# USB.net
KiCad netlist of a schematic drawn in Altium Designer
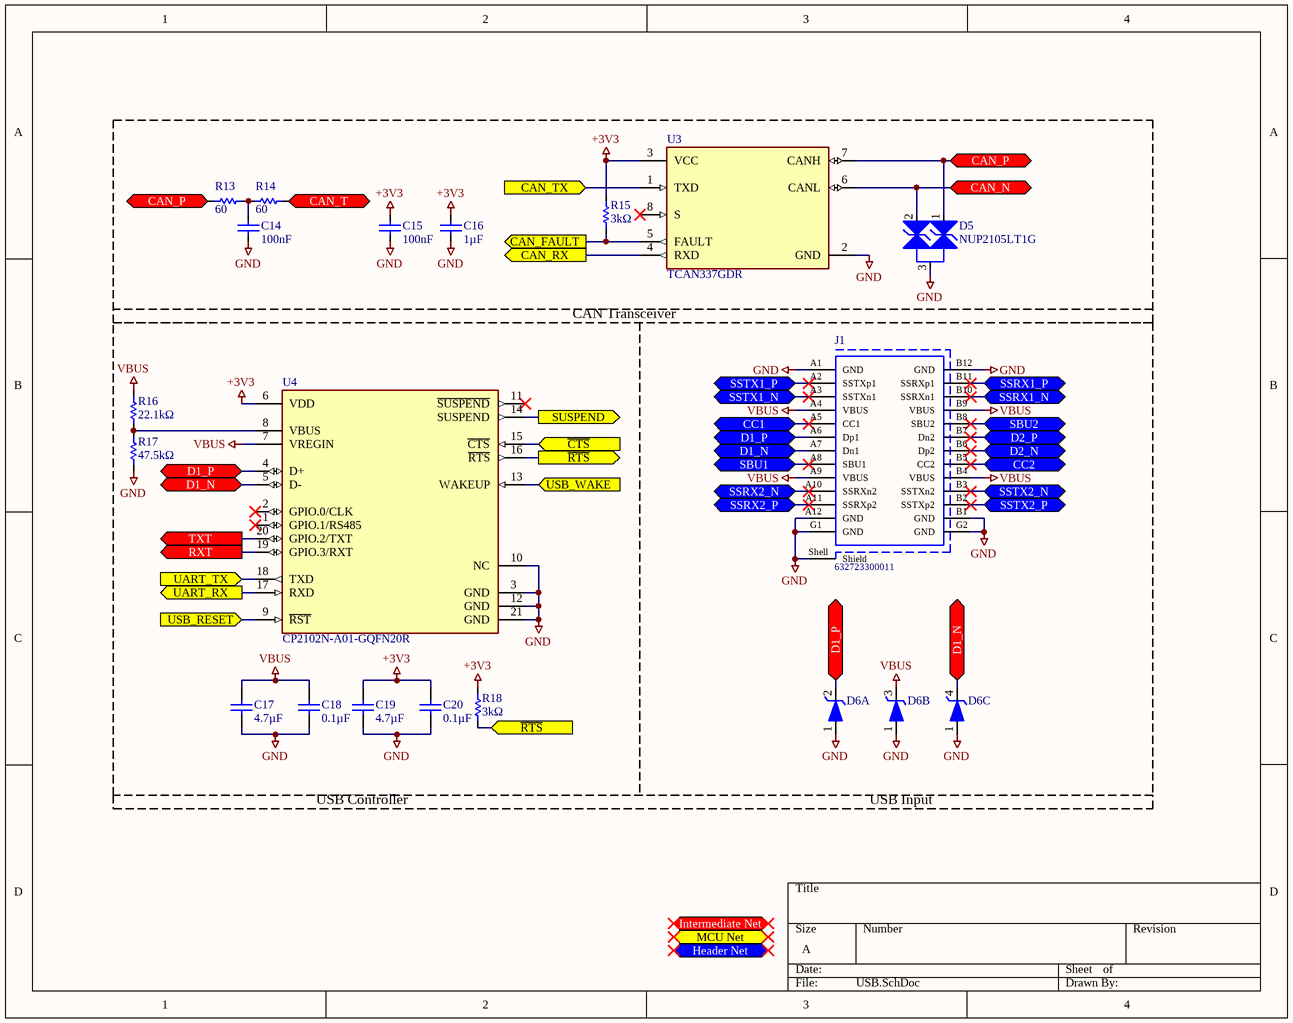
[diagram p0: USB.SchDoc]

(export (version "E")
  (design (tool "Eeschema 10.0.6"))
  (components
    (comp (ref "C14")
      (value "100nF")
      (footprint "1608[0603]")
      (description "Capacitor (Semiconductor SIM Model)")
      (fields (field (name "PUBLISHER") "Altium Limited"))
      (libsource (lib "Miscellaneous Devices") (part "Cap Semi"))
    )
    (comp (ref "C15")
      (value "100nF")
      (footprint "1608[0603]")
      (description "Capacitor (Semiconductor SIM Model)")
      (fields (field (name "PUBLISHER") "Altium Limited"))
      (libsource (lib "Miscellaneous Devices") (part "Cap Semi"))
    )
    (comp (ref "C16")
      (value "1µF")
      (footprint "1608[0603]")
      (description "Capacitor (Semiconductor SIM Model)")
      (fields (field (name "Comment") "100nF") (field (name "PUBLISHER") "Altium Limited"))
      (libsource (lib "Miscellaneous Devices") (part "Cap Semi"))
    )
    (comp (ref "C17")
      (value "4.7µF")
      (footprint "1608[0603]")
      (description "Capacitor (Semiconductor SIM Model)")
      (fields (field (name "Comment") "100nF") (field (name "PUBLISHER") "Altium Limited"))
      (libsource (lib "") (part "Cap Semi_1"))
    )
    (comp (ref "C18")
      (value "0.1µF")
      (footprint "1608[0603]")
      (description "Capacitor (Semiconductor SIM Model)")
      (fields (field (name "Comment") "100nF") (field (name "PUBLISHER") "Altium Limited"))
      (libsource (lib "") (part "Cap Semi_1"))
    )
    (comp (ref "C19")
      (value "4.7µF")
      (footprint "1608[0603]")
      (description "Capacitor (Semiconductor SIM Model)")
      (fields (field (name "Comment") "100nF") (field (name "PUBLISHER") "Altium Limited"))
      (libsource (lib "") (part "Cap Semi_1"))
    )
    (comp (ref "C20")
      (value "0.1µF")
      (footprint "1608[0603]")
      (description "Capacitor (Semiconductor SIM Model)")
      (fields (field (name "Comment") "100nF") (field (name "PUBLISHER") "Altium Limited"))
      (libsource (lib "") (part "Cap Semi_1"))
    )
    (comp (ref "D5")
      (value "NUP2105LT1G")
      (footprint "ONSC-SOT-23-3-318-08_V")
      (description "Dual Line CAN Bus Protector, 3-Pin SOT-23, Pb-Free, Tape and Reel")
      (fields (field (name "MANUFACTURER") "On Semiconductor"))
      (libsource (lib "Altium Content Vault") (part "ONSC-NUP21X5X-SOT-23-3-318-08"))
    )
    (comp (ref "D6")
      (value "SP0503BAHTG")
      (footprint "SOT143")
      (description "TVS Diode Array, 30 pF, 30 KV, -40 to 85 degC, 4-Pin SOT143, RoHS, Tape and Reel")
      (fields (field (name "MANUFACTURER") "Littelfuse"))
      (libsource (lib "DWM_SCH") (part "LFUS-SP0503BAHTG-SOT143-4"))
    )
    (comp (ref "J1")
      (value "632723300011")
      (footprint "632723300011")
      (description "USB 3.1 Type C Receptacle WR-COM, Horizontal, SMT / THT")
      (fields (field (name "MANUFACTURER") "Wurth Elektronik") (field (name "PUBLISHER") "WurthElektronik"))
      (libsource (lib "Altium Content Vault") (part "WE-632723X00011"))
    )
    (comp (ref "R13")
      (value "60")
      (footprint "1608[0603]")
      (description "Resistor")
      (fields (field (name "Comment") "60 ohm") (field (name "PUBLISHER") "Altium Limited"))
      (libsource (lib "Miscellaneous Devices") (part "Res1"))
    )
    (comp (ref "R14")
      (value "60")
      (footprint "1608[0603]")
      (description "Resistor")
      (fields (field (name "Comment") "60 ohm") (field (name "PUBLISHER") "Altium Limited"))
      (libsource (lib "Miscellaneous Devices") (part "Res1"))
    )
    (comp (ref "R15")
      (value "3kΩ")
      (footprint "1608[0603]")
      (description "Resistor")
      (fields (field (name "Comment") "3k") (field (name "PUBLISHER") "Altium Limited"))
      (libsource (lib "Miscellaneous Devices") (part "Res1"))
    )
    (comp (ref "R16")
      (value "22.1kΩ")
      (footprint "1608[0603]")
      (description "Resistor")
      (fields (field (name "Comment") "3k") (field (name "PUBLISHER") "Altium Limited"))
      (libsource (lib "Miscellaneous Devices") (part "Res1"))
    )
    (comp (ref "R17")
      (value "47.5kΩ")
      (footprint "1608[0603]")
      (description "Resistor")
      (fields (field (name "Comment") "3k") (field (name "PUBLISHER") "Altium Limited"))
      (libsource (lib "Miscellaneous Devices") (part "Res1"))
    )
    (comp (ref "R18")
      (value "3kΩ")
      (footprint "1608[0603]")
      (description "Resistor")
      (fields (field (name "Comment") "3k") (field (name "PUBLISHER") "Altium Limited"))
      (libsource (lib "Miscellaneous Devices") (part "Res1"))
    )
    (comp (ref "U3")
      (value "TCAN337GDR")
      (footprint "FP-D0008A-IPC_C")
      (description "IC TRANSCEIVER 1/1 8SOIC")
      (libsource (lib "Altium Content Vault") (part "a138acb6fe070981c36b7847827baee"))
    )
    (comp (ref "U4")
      (value "CP2102N-A01-GQFN20R")
      (footprint "FP-CP2102N-A01-GQFN20R-MFG")
      (description "IC BRIDGE USB TO UART 20QFN")
      (fields
        (field (name "OCTOPART") "https://octopart.com/cp2102n-a01-gqfn20r-silicon+labs-76789142")
        (field (name "MANUFACTURER") "Silicon Labs")
      )
      (libsource (lib "Altium Content Vault") (part "7ffc527c57c30584f1c8e0db5a92d37"))
    )
  )
  (nets
    (net (code "1") (name "+3V3") (class "Default")
      (node (ref "C15") (pin "1") (pinfunction "1_1") (pintype "passive"))
      (node (ref "C16") (pin "1") (pinfunction "1_1") (pintype "passive"))
      (node (ref "C19") (pin "1") (pinfunction "1_1") (pintype "passive"))
      (node (ref "C20") (pin "1") (pinfunction "1_1") (pintype "passive"))
      (node (ref "R15") (pin "1") (pinfunction "1_1") (pintype "passive"))
      (node (ref "R18") (pin "1") (pinfunction "1_1") (pintype "passive"))
      (node (ref "U3") (pin "3") (pinfunction "VCC_3") (pintype "power_in"))
      (node (ref "U4") (pin "6") (pinfunction "VDD_6") (pintype "power_in"))
    )
    (net (code "2") (name "/CAN_FAULT") (class "Default")
      (node (ref "R15") (pin "2") (pinfunction "2_2") (pintype "passive"))
      (node (ref "U3") (pin "5") (pinfunction "FAULT_5") (pintype "output"))
    )
    (net (code "3") (name "/CAN_N") (class "Default")
      (node (ref "D5") (pin "2") (pinfunction "K_2") (pintype "passive"))
      (node (ref "U3") (pin "6") (pinfunction "CANL_6") (pintype "bidirectional"))
    )
    (net (code "4") (name "/CAN_P") (class "Default")
      (node (ref "D5") (pin "1") (pinfunction "K_1") (pintype "passive"))
      (node (ref "R13") (pin "2") (pinfunction "2_2") (pintype "passive"))
      (node (ref "U3") (pin "7") (pinfunction "CANH_7") (pintype "bidirectional"))
    )
    (net (code "5") (name "/CAN_RX") (class "Default")
      (node (ref "U3") (pin "4") (pinfunction "RXD_4") (pintype "output"))
    )
    (net (code "6") (name "/CAN_T") (class "Default")
      (node (ref "R14") (pin "1") (pinfunction "1_1") (pintype "passive"))
    )
    (net (code "7") (name "/CAN_TX") (class "Default")
      (node (ref "U3") (pin "1") (pinfunction "TXD_1") (pintype "input"))
    )
    (net (code "8") (name "/CC1") (class "Default")
      (node (ref "J1") (pin "A5") (pinfunction "CC1_A5") (pintype "passive+no_connect"))
    )
    (net (code "9") (name "/CC2") (class "Default")
      (node (ref "J1") (pin "B5") (pinfunction "CC2_B5") (pintype "passive+no_connect"))
    )
    (net (code "10") (name "/D1_N") (class "Default")
      (node (ref "D6") (pin "4") (pinfunction "4_4") (pintype "passive"))
      (node (ref "J1") (pin "A7") (pinfunction "Dn1_A7") (pintype "passive"))
      (node (ref "U4") (pin "5") (pinfunction "D-_5") (pintype "bidirectional"))
    )
    (net (code "11") (name "/D1_P") (class "Default")
      (node (ref "D6") (pin "2") (pinfunction "2_2") (pintype "passive"))
      (node (ref "J1") (pin "A6") (pinfunction "Dp1_A6") (pintype "passive"))
      (node (ref "U4") (pin "4") (pinfunction "D+_4") (pintype "bidirectional"))
    )
    (net (code "12") (name "/D2_N") (class "Default")
      (node (ref "J1") (pin "B6") (pinfunction "Dp2_B6") (pintype "passive+no_connect"))
    )
    (net (code "13") (name "/D2_P") (class "Default")
      (node (ref "J1") (pin "B7") (pinfunction "Dn2_B7") (pintype "passive+no_connect"))
    )
    (net (code "17") (name "/RXT") (class "Default")
      (node (ref "U4") (pin "19") (pinfunction "GPIO.3/RXT_19") (pintype "bidirectional"))
    )
    (net (code "18") (name "/SBU1") (class "Default")
      (node (ref "J1") (pin "A8") (pinfunction "SBU1_A8") (pintype "passive+no_connect"))
    )
    (net (code "19") (name "/SBU2") (class "Default")
      (node (ref "J1") (pin "B8") (pinfunction "SBU2_B8") (pintype "passive+no_connect"))
    )
    (net (code "20") (name "/SSRX1_N") (class "Default")
      (node (ref "J1") (pin "B10") (pinfunction "SSRXn1_B10") (pintype "passive+no_connect"))
    )
    (net (code "21") (name "/SSRX1_P") (class "Default")
      (node (ref "J1") (pin "B11") (pinfunction "SSRXp1_B11") (pintype "passive+no_connect"))
    )
    (net (code "22") (name "/SSRX2_N") (class "Default")
      (node (ref "J1") (pin "A10") (pinfunction "SSRXn2_A10") (pintype "passive+no_connect"))
    )
    (net (code "23") (name "/SSRX2_P") (class "Default")
      (node (ref "J1") (pin "A11") (pinfunction "SSRXp2_A11") (pintype "passive+no_connect"))
    )
    (net (code "24") (name "/SSTX1_N") (class "Default")
      (node (ref "J1") (pin "A3") (pinfunction "SSTXn1_A3") (pintype "passive+no_connect"))
    )
    (net (code "25") (name "/SSTX1_P") (class "Default")
      (node (ref "J1") (pin "A2") (pinfunction "SSTXp1_A2") (pintype "passive+no_connect"))
    )
    (net (code "26") (name "/SSTX2_N") (class "Default")
      (node (ref "J1") (pin "B3") (pinfunction "SSTXn2_B3") (pintype "passive+no_connect"))
    )
    (net (code "27") (name "/SSTX2_P") (class "Default")
      (node (ref "J1") (pin "B2") (pinfunction "SSTXp2_B2") (pintype "passive+no_connect"))
    )
    (net (code "28") (name "/SUSPEND") (class "Default")
      (node (ref "U4") (pin "14") (pinfunction "SUSPEND_14") (pintype "output"))
    )
    (net (code "29") (name "/TXT") (class "Default")
      (node (ref "U4") (pin "20") (pinfunction "GPIO.2/TXT_20") (pintype "bidirectional"))
    )
    (net (code "30") (name "/UART_RX") (class "Default")
      (node (ref "U4") (pin "17") (pinfunction "RXD_17") (pintype "input"))
    )
    (net (code "31") (name "/UART_TX") (class "Default")
      (node (ref "U4") (pin "18") (pinfunction "TXD_18") (pintype "output"))
    )
    (net (code "32") (name "/USB_RESET") (class "Default")
      (node (ref "U4") (pin "9") (pinfunction "~{RST}_9") (pintype "input"))
    )
    (net (code "33") (name "/USB_WAKE") (class "Default")
      (node (ref "U4") (pin "13") (pinfunction "WAKEUP_13") (pintype "input"))
    )
    (net (code "34") (name "/~{CTS}") (class "Default")
      (node (ref "U4") (pin "15") (pinfunction "~{CTS}_15") (pintype "input"))
    )
    (net (code "35") (name "/~{RTS}") (class "Default")
      (node (ref "R18") (pin "2") (pinfunction "2_2") (pintype "passive"))
      (node (ref "U4") (pin "16") (pinfunction "~{RTS}_16") (pintype "output"))
    )
    (net (code "36") (name "GND") (class "Default")
      (node (ref "C14") (pin "2") (pinfunction "2_2") (pintype "passive"))
      (node (ref "C15") (pin "2") (pinfunction "2_2") (pintype "passive"))
      (node (ref "C16") (pin "2") (pinfunction "2_2") (pintype "passive"))
      (node (ref "C17") (pin "2") (pinfunction "2_2") (pintype "passive"))
      (node (ref "C18") (pin "2") (pinfunction "2_2") (pintype "passive"))
      (node (ref "C19") (pin "2") (pinfunction "2_2") (pintype "passive"))
      (node (ref "C20") (pin "2") (pinfunction "2_2") (pintype "passive"))
      (node (ref "D5") (pin "3") (pinfunction "K_3") (pintype "passive"))
      (node (ref "D6") (pin "1") (pinfunction "1_1") (pintype "passive"))
      (node (ref "J1") (pin "A1") (pinfunction "GND_A1") (pintype "passive"))
      (node (ref "J1") (pin "A12") (pinfunction "GND_A12") (pintype "passive"))
      (node (ref "J1") (pin "B1") (pinfunction "GND_B1") (pintype "passive"))
      (node (ref "J1") (pin "B12") (pinfunction "GND_B12") (pintype "passive"))
      (node (ref "J1") (pin "G1") (pinfunction "GND_G1") (pintype "passive"))
      (node (ref "J1") (pin "G2") (pinfunction "GND_G2") (pintype "passive"))
      (node (ref "J1") (pin "Shell") (pinfunction "Shield_Shell") (pintype "passive"))
      (node (ref "R17") (pin "2") (pinfunction "2_2") (pintype "passive"))
      (node (ref "U3") (pin "2") (pinfunction "GND_2") (pintype "power_in"))
      (node (ref "U4") (pin "10") (pinfunction "NC_10") (pintype "passive"))
      (node (ref "U4") (pin "12") (pinfunction "GND_12") (pintype "power_in"))
      (node (ref "U4") (pin "21") (pinfunction "GND_21") (pintype "power_in"))
      (node (ref "U4") (pin "3") (pinfunction "GND_3") (pintype "power_in"))
    )
    (net (code "37") (name "Net-(C14-Pad1)") (class "Default")
      (node (ref "C14") (pin "1") (pinfunction "1_1") (pintype "passive"))
      (node (ref "R13") (pin "1") (pinfunction "1_1") (pintype "passive"))
      (node (ref "R14") (pin "2") (pinfunction "2_2") (pintype "passive"))
    )
    (net (code "38") (name "Net-(U4-VBUS)") (class "Default")
      (node (ref "R16") (pin "2") (pinfunction "2_2") (pintype "passive"))
      (node (ref "R17") (pin "1") (pinfunction "1_1") (pintype "passive"))
      (node (ref "U4") (pin "8") (pinfunction "VBUS_8") (pintype "power_in"))
    )
    (net (code "39") (name "VBUS") (class "Default")
      (node (ref "C17") (pin "1") (pinfunction "1_1") (pintype "passive"))
      (node (ref "C18") (pin "1") (pinfunction "1_1") (pintype "passive"))
      (node (ref "D6") (pin "3") (pinfunction "3_3") (pintype "passive"))
      (node (ref "J1") (pin "A4") (pinfunction "VBUS_A4") (pintype "passive"))
      (node (ref "J1") (pin "A9") (pinfunction "VBUS_A9") (pintype "passive"))
      (node (ref "J1") (pin "B4") (pinfunction "VBUS_B4") (pintype "passive"))
      (node (ref "J1") (pin "B9") (pinfunction "VBUS_B9") (pintype "passive"))
      (node (ref "R16") (pin "1") (pinfunction "1_1") (pintype "passive"))
      (node (ref "U4") (pin "7") (pinfunction "VREGIN_7") (pintype "power_in"))
    )
    (net (code "40") (name "unconnected-(U3-S-Pad8)") (class "Default")
      (node (ref "U3") (pin "8") (pinfunction "S_8") (pintype "input+no_connect"))
    )
    (net (code "41") (name "unconnected-(U4-GPIO.0{slash}CLK-Pad2)") (class "Default")
      (node (ref "U4") (pin "2") (pinfunction "GPIO.0/CLK_2") (pintype "bidirectional+no_connect"))
    )
    (net (code "42") (name "unconnected-(U4-GPIO.1{slash}RS485-Pad1)") (class "Default")
      (node (ref "U4") (pin "1") (pinfunction "GPIO.1/RS485_1") (pintype "bidirectional+no_connect"))
    )
    (net (code "43") (name "unconnected-(U4-~{SUSPEND}-Pad11)") (class "Default")
      (node (ref "U4") (pin "11") (pinfunction "~{SUSPEND}_11") (pintype "output+no_connect"))
    )
  )
)
